# Servo.net
KiCad netlist of a schematic drawn in EAGLE
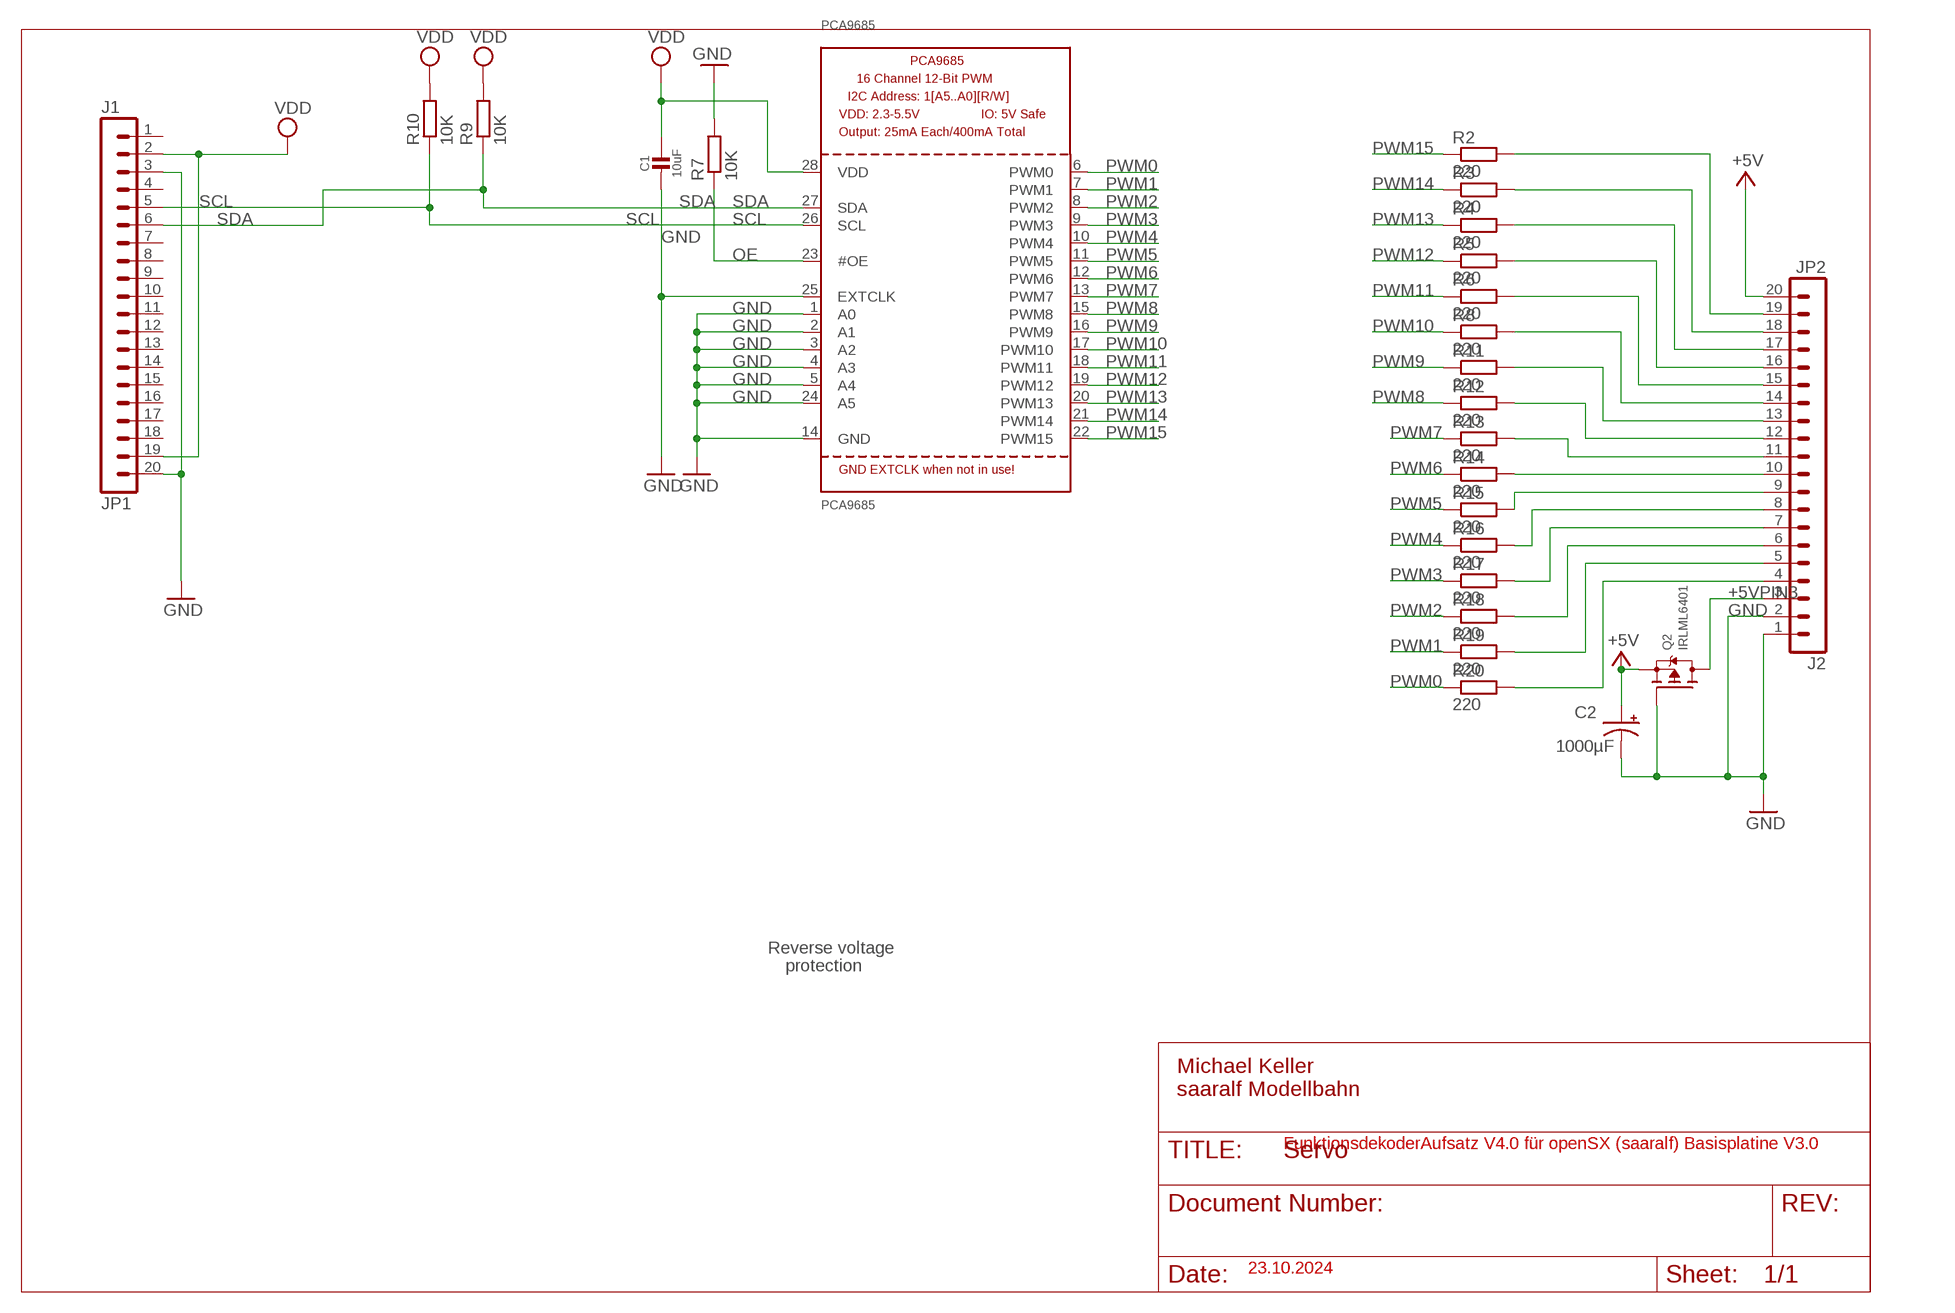
[diagram p0: schematic, sheet 1]

(export (version "E")
  (design (tool "Eeschema 10.0.6"))
  (components
    (comp (ref "C1")
      (value "10uF")
      (footprint "eagle-import:0805-NO")
      (libsource (lib "eagle-import") (part "CAP_CERAMIC0805-NOOUTLINE"))
    )
    (comp (ref "C2")
      (value "1000µF")
      (footprint "eagle-import:E3,5-8")
      (libsource (lib "eagle-import") (part "CPOL-USE3.5-8"))
    )
    (comp (ref "JP1")
      (value "J1")
      (footprint "eagle-import:MA20-1")
      (libsource (lib "eagle-import") (part "MA20-1"))
    )
    (comp (ref "JP2")
      (value "J2")
      (footprint "eagle-import:MA20-1")
      (libsource (lib "eagle-import") (part "MA20-1"))
    )
    (comp (ref "PCA9685")
      (value "PCA9685")
      (footprint "eagle-import:TSSOP28")
      (libsource (lib "eagle-import") (part "PCA9685"))
    )
    (comp (ref "Q2")
      (value "IRLML6401")
      (footprint "eagle-import:SOT23-WIDE")
      (libsource (lib "eagle-import") (part "MOSFET-PWIDE"))
    )
    (comp (ref "R2")
      (value "220")
      (footprint "eagle-import:M0805")
      (libsource (lib "eagle-import") (part "R-EU_M0805"))
    )
    (comp (ref "R3")
      (value "220")
      (footprint "eagle-import:M0805")
      (libsource (lib "eagle-import") (part "R-EU_M0805"))
    )
    (comp (ref "R4")
      (value "220")
      (footprint "eagle-import:M0805")
      (libsource (lib "eagle-import") (part "R-EU_M0805"))
    )
    (comp (ref "R5")
      (value "220")
      (footprint "eagle-import:M0805")
      (libsource (lib "eagle-import") (part "R-EU_M0805"))
    )
    (comp (ref "R6")
      (value "220")
      (footprint "eagle-import:M0805")
      (libsource (lib "eagle-import") (part "R-EU_M0805"))
    )
    (comp (ref "R7")
      (value "10K")
      (footprint "eagle-import:M0805")
      (libsource (lib "eagle-import") (part "R-EU_M0805"))
    )
    (comp (ref "R8")
      (value "220")
      (footprint "eagle-import:M0805")
      (libsource (lib "eagle-import") (part "R-EU_M0805"))
    )
    (comp (ref "R9")
      (value "10K")
      (footprint "eagle-import:M0805")
      (libsource (lib "eagle-import") (part "R-EU_M0805"))
    )
    (comp (ref "R10")
      (value "10K")
      (footprint "eagle-import:M0805")
      (libsource (lib "eagle-import") (part "R-EU_M0805"))
    )
    (comp (ref "R11")
      (value "220")
      (footprint "eagle-import:M0805")
      (libsource (lib "eagle-import") (part "R-EU_M0805"))
    )
    (comp (ref "R12")
      (value "220")
      (footprint "eagle-import:M0805")
      (libsource (lib "eagle-import") (part "R-EU_M0805"))
    )
    (comp (ref "R13")
      (value "220")
      (footprint "eagle-import:M0805")
      (libsource (lib "eagle-import") (part "R-EU_M0805"))
    )
    (comp (ref "R14")
      (value "220")
      (footprint "eagle-import:M0805")
      (libsource (lib "eagle-import") (part "R-EU_M0805"))
    )
    (comp (ref "R15")
      (value "220")
      (footprint "eagle-import:M0805")
      (libsource (lib "eagle-import") (part "R-EU_M0805"))
    )
    (comp (ref "R16")
      (value "220")
      (footprint "eagle-import:M0805")
      (libsource (lib "eagle-import") (part "R-EU_M0805"))
    )
    (comp (ref "R17")
      (value "220")
      (footprint "eagle-import:M0805")
      (libsource (lib "eagle-import") (part "R-EU_M0805"))
    )
    (comp (ref "R18")
      (value "220")
      (footprint "eagle-import:M0805")
      (libsource (lib "eagle-import") (part "R-EU_M0805"))
    )
    (comp (ref "R19")
      (value "220")
      (footprint "eagle-import:M0805")
      (libsource (lib "eagle-import") (part "R-EU_M0805"))
    )
    (comp (ref "R20")
      (value "220")
      (footprint "eagle-import:M0805")
      (libsource (lib "eagle-import") (part "R-EU_M0805"))
    )
  )
  (nets
    (net (code "1") (name "+5V") (class "Default")
      (node (ref "C2") (pin "+") (pinfunction "+_+") (pintype "passive"))
      (node (ref "JP2") (pin "20") (pinfunction "20_20") (pintype "passive"))
      (node (ref "Q2") (pin "2") (pinfunction "S_2") (pintype "passive"))
    )
    (net (code "2") (name "/+5VPIN3") (class "Default")
      (node (ref "JP2") (pin "3") (pinfunction "3_3") (pintype "passive"))
      (node (ref "Q2") (pin "3") (pinfunction "D_3") (pintype "passive"))
    )
    (net (code "3") (name "/OE") (class "Default")
      (node (ref "PCA9685") (pin "23") (pinfunction "#OE_23") (pintype "input"))
      (node (ref "R7") (pin "1") (pinfunction "1_1") (pintype "passive"))
    )
    (net (code "4") (name "/PWM0") (class "Default")
      (node (ref "PCA9685") (pin "6") (pinfunction "PWM0_6") (pintype "output"))
      (node (ref "R20") (pin "1") (pinfunction "1_1") (pintype "passive"))
    )
    (net (code "5") (name "/PWM1") (class "Default")
      (node (ref "PCA9685") (pin "7") (pinfunction "PWM1_7") (pintype "output"))
      (node (ref "R19") (pin "1") (pinfunction "1_1") (pintype "passive"))
    )
    (net (code "6") (name "/PWM2") (class "Default")
      (node (ref "PCA9685") (pin "8") (pinfunction "PWM2_8") (pintype "output"))
      (node (ref "R18") (pin "1") (pinfunction "1_1") (pintype "passive"))
    )
    (net (code "7") (name "/PWM3") (class "Default")
      (node (ref "PCA9685") (pin "9") (pinfunction "PWM3_9") (pintype "output"))
      (node (ref "R17") (pin "1") (pinfunction "1_1") (pintype "passive"))
    )
    (net (code "8") (name "/PWM4") (class "Default")
      (node (ref "PCA9685") (pin "10") (pinfunction "PWM4_10") (pintype "output"))
      (node (ref "R16") (pin "1") (pinfunction "1_1") (pintype "passive"))
    )
    (net (code "9") (name "/PWM5") (class "Default")
      (node (ref "PCA9685") (pin "11") (pinfunction "PWM5_11") (pintype "output"))
      (node (ref "R15") (pin "1") (pinfunction "1_1") (pintype "passive"))
    )
    (net (code "10") (name "/PWM6") (class "Default")
      (node (ref "PCA9685") (pin "12") (pinfunction "PWM6_12") (pintype "output"))
      (node (ref "R14") (pin "1") (pinfunction "1_1") (pintype "passive"))
    )
    (net (code "11") (name "/PWM7") (class "Default")
      (node (ref "PCA9685") (pin "13") (pinfunction "PWM7_13") (pintype "output"))
      (node (ref "R13") (pin "1") (pinfunction "1_1") (pintype "passive"))
    )
    (net (code "12") (name "/PWM8") (class "Default")
      (node (ref "PCA9685") (pin "15") (pinfunction "PWM8_15") (pintype "output"))
      (node (ref "R12") (pin "1") (pinfunction "1_1") (pintype "passive"))
    )
    (net (code "13") (name "/PWM9") (class "Default")
      (node (ref "PCA9685") (pin "16") (pinfunction "PWM9_16") (pintype "output"))
      (node (ref "R11") (pin "1") (pinfunction "1_1") (pintype "passive"))
    )
    (net (code "14") (name "/PWM10") (class "Default")
      (node (ref "PCA9685") (pin "17") (pinfunction "PWM10_17") (pintype "output"))
      (node (ref "R8") (pin "1") (pinfunction "1_1") (pintype "passive"))
    )
    (net (code "15") (name "/PWM11") (class "Default")
      (node (ref "PCA9685") (pin "18") (pinfunction "PWM11_18") (pintype "output"))
      (node (ref "R6") (pin "1") (pinfunction "1_1") (pintype "passive"))
    )
    (net (code "16") (name "/PWM12") (class "Default")
      (node (ref "PCA9685") (pin "19") (pinfunction "PWM12_19") (pintype "output"))
      (node (ref "R5") (pin "1") (pinfunction "1_1") (pintype "passive"))
    )
    (net (code "17") (name "/PWM13") (class "Default")
      (node (ref "PCA9685") (pin "20") (pinfunction "PWM13_20") (pintype "output"))
      (node (ref "R4") (pin "1") (pinfunction "1_1") (pintype "passive"))
    )
    (net (code "18") (name "/PWM14") (class "Default")
      (node (ref "PCA9685") (pin "21") (pinfunction "PWM14_21") (pintype "output"))
      (node (ref "R3") (pin "1") (pinfunction "1_1") (pintype "passive"))
    )
    (net (code "19") (name "/PWM15") (class "Default")
      (node (ref "PCA9685") (pin "22") (pinfunction "PWM15_22") (pintype "output"))
      (node (ref "R2") (pin "1") (pinfunction "1_1") (pintype "passive"))
    )
    (net (code "20") (name "/SCL") (class "Default")
      (node (ref "JP1") (pin "5") (pinfunction "5_5") (pintype "passive"))
      (node (ref "PCA9685") (pin "26") (pinfunction "SCL_26") (pintype "bidirectional"))
      (node (ref "R10") (pin "1") (pinfunction "1_1") (pintype "passive"))
    )
    (net (code "21") (name "/SDA") (class "Default")
      (node (ref "JP1") (pin "6") (pinfunction "6_6") (pintype "passive"))
      (node (ref "PCA9685") (pin "27") (pinfunction "SDA_27") (pintype "bidirectional"))
      (node (ref "R9") (pin "1") (pinfunction "1_1") (pintype "passive"))
    )
    (net (code "22") (name "GND") (class "Default")
      (node (ref "C1") (pin "2") (pinfunction "2_2") (pintype "passive"))
      (node (ref "C2") (pin "-") (pinfunction "-_-") (pintype "passive"))
      (node (ref "JP1") (pin "20") (pinfunction "20_20") (pintype "passive"))
      (node (ref "JP1") (pin "3") (pinfunction "3_3") (pintype "passive"))
      (node (ref "JP2") (pin "1") (pinfunction "1_1") (pintype "passive"))
      (node (ref "JP2") (pin "2") (pinfunction "2_2") (pintype "passive"))
      (node (ref "PCA9685") (pin "1") (pinfunction "A0_1") (pintype "bidirectional"))
      (node (ref "PCA9685") (pin "14") (pinfunction "GND_14") (pintype "power_in"))
      (node (ref "PCA9685") (pin "2") (pinfunction "A1_2") (pintype "bidirectional"))
      (node (ref "PCA9685") (pin "24") (pinfunction "A5_24") (pintype "bidirectional"))
      (node (ref "PCA9685") (pin "25") (pinfunction "EXTCLK_25") (pintype "input"))
      (node (ref "PCA9685") (pin "3") (pinfunction "A2_3") (pintype "bidirectional"))
      (node (ref "PCA9685") (pin "4") (pinfunction "A3_4") (pintype "bidirectional"))
      (node (ref "PCA9685") (pin "5") (pinfunction "A4_5") (pintype "bidirectional"))
      (node (ref "Q2") (pin "1") (pinfunction "G_1") (pintype "passive"))
      (node (ref "R7") (pin "2") (pinfunction "2_2") (pintype "passive"))
    )
    (net (code "23") (name "Net-(JP2-Pad4)") (class "Default")
      (node (ref "JP2") (pin "4") (pinfunction "4_4") (pintype "passive"))
      (node (ref "R20") (pin "2") (pinfunction "2_2") (pintype "passive"))
    )
    (net (code "24") (name "Net-(JP2-Pad5)") (class "Default")
      (node (ref "JP2") (pin "5") (pinfunction "5_5") (pintype "passive"))
      (node (ref "R19") (pin "2") (pinfunction "2_2") (pintype "passive"))
    )
    (net (code "25") (name "Net-(JP2-Pad6)") (class "Default")
      (node (ref "JP2") (pin "6") (pinfunction "6_6") (pintype "passive"))
      (node (ref "R18") (pin "2") (pinfunction "2_2") (pintype "passive"))
    )
    (net (code "26") (name "Net-(JP2-Pad7)") (class "Default")
      (node (ref "JP2") (pin "7") (pinfunction "7_7") (pintype "passive"))
      (node (ref "R17") (pin "2") (pinfunction "2_2") (pintype "passive"))
    )
    (net (code "27") (name "Net-(JP2-Pad8)") (class "Default")
      (node (ref "JP2") (pin "8") (pinfunction "8_8") (pintype "passive"))
      (node (ref "R16") (pin "2") (pinfunction "2_2") (pintype "passive"))
    )
    (net (code "28") (name "Net-(JP2-Pad9)") (class "Default")
      (node (ref "JP2") (pin "9") (pinfunction "9_9") (pintype "passive"))
      (node (ref "R15") (pin "2") (pinfunction "2_2") (pintype "passive"))
    )
    (net (code "29") (name "Net-(JP2-Pad10)") (class "Default")
      (node (ref "JP2") (pin "10") (pinfunction "10_10") (pintype "passive"))
      (node (ref "R14") (pin "2") (pinfunction "2_2") (pintype "passive"))
    )
    (net (code "30") (name "Net-(JP2-Pad11)") (class "Default")
      (node (ref "JP2") (pin "11") (pinfunction "11_11") (pintype "passive"))
      (node (ref "R13") (pin "2") (pinfunction "2_2") (pintype "passive"))
    )
    (net (code "31") (name "Net-(JP2-Pad12)") (class "Default")
      (node (ref "JP2") (pin "12") (pinfunction "12_12") (pintype "passive"))
      (node (ref "R12") (pin "2") (pinfunction "2_2") (pintype "passive"))
    )
    (net (code "32") (name "Net-(JP2-Pad13)") (class "Default")
      (node (ref "JP2") (pin "13") (pinfunction "13_13") (pintype "passive"))
      (node (ref "R11") (pin "2") (pinfunction "2_2") (pintype "passive"))
    )
    (net (code "33") (name "Net-(JP2-Pad14)") (class "Default")
      (node (ref "JP2") (pin "14") (pinfunction "14_14") (pintype "passive"))
      (node (ref "R8") (pin "2") (pinfunction "2_2") (pintype "passive"))
    )
    (net (code "34") (name "Net-(JP2-Pad15)") (class "Default")
      (node (ref "JP2") (pin "15") (pinfunction "15_15") (pintype "passive"))
      (node (ref "R6") (pin "2") (pinfunction "2_2") (pintype "passive"))
    )
    (net (code "35") (name "Net-(JP2-Pad16)") (class "Default")
      (node (ref "JP2") (pin "16") (pinfunction "16_16") (pintype "passive"))
      (node (ref "R5") (pin "2") (pinfunction "2_2") (pintype "passive"))
    )
    (net (code "36") (name "Net-(JP2-Pad17)") (class "Default")
      (node (ref "JP2") (pin "17") (pinfunction "17_17") (pintype "passive"))
      (node (ref "R4") (pin "2") (pinfunction "2_2") (pintype "passive"))
    )
    (net (code "37") (name "Net-(JP2-Pad18)") (class "Default")
      (node (ref "JP2") (pin "18") (pinfunction "18_18") (pintype "passive"))
      (node (ref "R3") (pin "2") (pinfunction "2_2") (pintype "passive"))
    )
    (net (code "38") (name "Net-(JP2-Pad19)") (class "Default")
      (node (ref "JP2") (pin "19") (pinfunction "19_19") (pintype "passive"))
      (node (ref "R2") (pin "2") (pinfunction "2_2") (pintype "passive"))
    )
    (net (code "39") (name "VDD") (class "Default")
      (node (ref "C1") (pin "1") (pinfunction "1_1") (pintype "passive"))
      (node (ref "JP1") (pin "19") (pinfunction "19_19") (pintype "passive"))
      (node (ref "JP1") (pin "2") (pinfunction "2_2") (pintype "passive"))
      (node (ref "PCA9685") (pin "28") (pinfunction "VDD_28") (pintype "power_in"))
      (node (ref "R10") (pin "2") (pinfunction "2_2") (pintype "passive"))
      (node (ref "R9") (pin "2") (pinfunction "2_2") (pintype "passive"))
    )
    (net (code "40") (name "unconnected-(JP1-Pad1)") (class "Default")
      (node (ref "JP1") (pin "1") (pinfunction "1_1") (pintype "passive"))
    )
    (net (code "41") (name "unconnected-(JP1-Pad4)") (class "Default")
      (node (ref "JP1") (pin "4") (pinfunction "4_4") (pintype "passive"))
    )
    (net (code "42") (name "unconnected-(JP1-Pad7)") (class "Default")
      (node (ref "JP1") (pin "7") (pinfunction "7_7") (pintype "passive"))
    )
    (net (code "43") (name "unconnected-(JP1-Pad8)") (class "Default")
      (node (ref "JP1") (pin "8") (pinfunction "8_8") (pintype "passive"))
    )
    (net (code "44") (name "unconnected-(JP1-Pad9)") (class "Default")
      (node (ref "JP1") (pin "9") (pinfunction "9_9") (pintype "passive"))
    )
    (net (code "45") (name "unconnected-(JP1-Pad10)") (class "Default")
      (node (ref "JP1") (pin "10") (pinfunction "10_10") (pintype "passive"))
    )
    (net (code "46") (name "unconnected-(JP1-Pad11)") (class "Default")
      (node (ref "JP1") (pin "11") (pinfunction "11_11") (pintype "passive"))
    )
    (net (code "47") (name "unconnected-(JP1-Pad12)") (class "Default")
      (node (ref "JP1") (pin "12") (pinfunction "12_12") (pintype "passive"))
    )
    (net (code "48") (name "unconnected-(JP1-Pad13)") (class "Default")
      (node (ref "JP1") (pin "13") (pinfunction "13_13") (pintype "passive"))
    )
    (net (code "49") (name "unconnected-(JP1-Pad14)") (class "Default")
      (node (ref "JP1") (pin "14") (pinfunction "14_14") (pintype "passive"))
    )
    (net (code "50") (name "unconnected-(JP1-Pad15)") (class "Default")
      (node (ref "JP1") (pin "15") (pinfunction "15_15") (pintype "passive"))
    )
    (net (code "51") (name "unconnected-(JP1-Pad16)") (class "Default")
      (node (ref "JP1") (pin "16") (pinfunction "16_16") (pintype "passive"))
    )
    (net (code "52") (name "unconnected-(JP1-Pad17)") (class "Default")
      (node (ref "JP1") (pin "17") (pinfunction "17_17") (pintype "passive"))
    )
    (net (code "53") (name "unconnected-(JP1-Pad18)") (class "Default")
      (node (ref "JP1") (pin "18") (pinfunction "18_18") (pintype "passive"))
    )
  )
)
